# Edgework.net
KiCad netlist of a schematic drawn in EAGLE
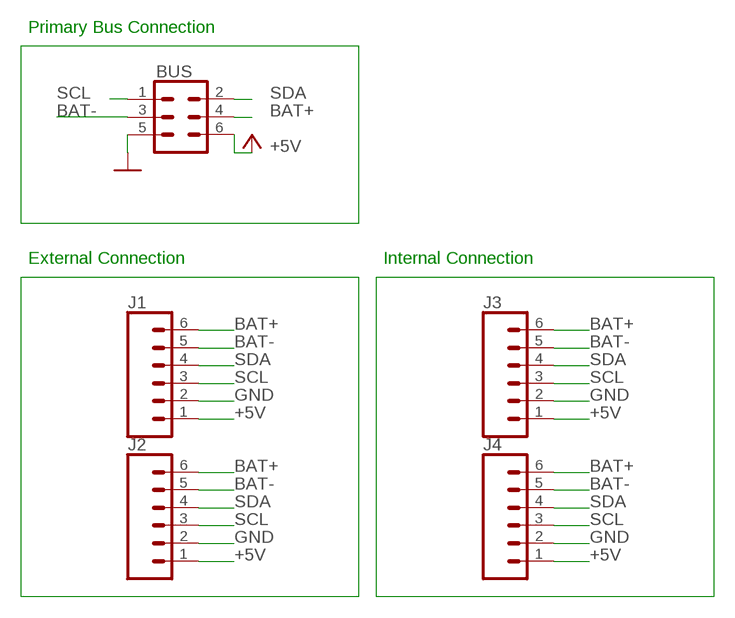
[diagram p0: schematic, sheet 1]

(export (version "E")
  (design (tool "Eeschema 10.0.6"))
  (components
    (comp (ref "BUS")
      (value "CONN_03X2SHROUD")
      (footprint "eagle-import:2X3-SHROUDED")
      (libsource (lib "eagle-import") (part "CONN_03X2SHROUD"))
    )
    (comp (ref "J1")
      (value "CONN_06NO_SILK_FEMALE_PTH")
      (footprint "eagle-import:1X06_NO_SILK")
      (libsource (lib "eagle-import") (part "CONN_06NO_SILK_FEMALE_PTH"))
    )
    (comp (ref "J2")
      (value "CONN_06NO_SILK_FEMALE_PTH")
      (footprint "eagle-import:1X06_NO_SILK")
      (libsource (lib "eagle-import") (part "CONN_06NO_SILK_FEMALE_PTH"))
    )
    (comp (ref "J3")
      (value "CONN_06NO_SILK_FEMALE_PTH")
      (footprint "eagle-import:1X06_NO_SILK")
      (libsource (lib "eagle-import") (part "CONN_06NO_SILK_FEMALE_PTH"))
    )
    (comp (ref "J4")
      (value "CONN_06NO_SILK_FEMALE_PTH")
      (footprint "eagle-import:1X06_NO_SILK")
      (libsource (lib "eagle-import") (part "CONN_06NO_SILK_FEMALE_PTH"))
    )
  )
  (nets
    (net (code "1") (name "+5V") (class "Default")
      (node (ref "BUS") (pin "6") (pinfunction "6_6") (pintype "bidirectional"))
      (node (ref "J1") (pin "1") (pinfunction "1_1") (pintype "passive"))
      (node (ref "J2") (pin "1") (pinfunction "1_1") (pintype "passive"))
      (node (ref "J3") (pin "1") (pinfunction "1_1") (pintype "passive"))
      (node (ref "J4") (pin "1") (pinfunction "1_1") (pintype "passive"))
    )
    (net (code "2") (name "/BAT+") (class "Default")
      (node (ref "BUS") (pin "4") (pinfunction "4_4") (pintype "bidirectional"))
      (node (ref "J1") (pin "6") (pinfunction "6_6") (pintype "passive"))
      (node (ref "J2") (pin "6") (pinfunction "6_6") (pintype "passive"))
      (node (ref "J3") (pin "6") (pinfunction "6_6") (pintype "passive"))
      (node (ref "J4") (pin "6") (pinfunction "6_6") (pintype "passive"))
    )
    (net (code "3") (name "/BAT-") (class "Default")
      (node (ref "BUS") (pin "3") (pinfunction "3_3") (pintype "bidirectional"))
      (node (ref "J1") (pin "5") (pinfunction "5_5") (pintype "passive"))
      (node (ref "J2") (pin "5") (pinfunction "5_5") (pintype "passive"))
      (node (ref "J3") (pin "5") (pinfunction "5_5") (pintype "passive"))
      (node (ref "J4") (pin "5") (pinfunction "5_5") (pintype "passive"))
    )
    (net (code "4") (name "/SCL") (class "Default")
      (node (ref "BUS") (pin "1") (pinfunction "1_1") (pintype "bidirectional"))
      (node (ref "J1") (pin "3") (pinfunction "3_3") (pintype "passive"))
      (node (ref "J2") (pin "3") (pinfunction "3_3") (pintype "passive"))
      (node (ref "J3") (pin "3") (pinfunction "3_3") (pintype "passive"))
      (node (ref "J4") (pin "3") (pinfunction "3_3") (pintype "passive"))
    )
    (net (code "5") (name "/SDA") (class "Default")
      (node (ref "BUS") (pin "2") (pinfunction "2_2") (pintype "bidirectional"))
      (node (ref "J1") (pin "4") (pinfunction "4_4") (pintype "passive"))
      (node (ref "J2") (pin "4") (pinfunction "4_4") (pintype "passive"))
      (node (ref "J3") (pin "4") (pinfunction "4_4") (pintype "passive"))
      (node (ref "J4") (pin "4") (pinfunction "4_4") (pintype "passive"))
    )
    (net (code "6") (name "GND") (class "Default")
      (node (ref "BUS") (pin "5") (pinfunction "5_5") (pintype "bidirectional"))
      (node (ref "J1") (pin "2") (pinfunction "2_2") (pintype "passive"))
      (node (ref "J2") (pin "2") (pinfunction "2_2") (pintype "passive"))
      (node (ref "J3") (pin "2") (pinfunction "2_2") (pintype "passive"))
      (node (ref "J4") (pin "2") (pinfunction "2_2") (pintype "passive"))
    )
  )
)
